# Input_Filter.net
KiCad netlist of a schematic drawn in Altium Designer
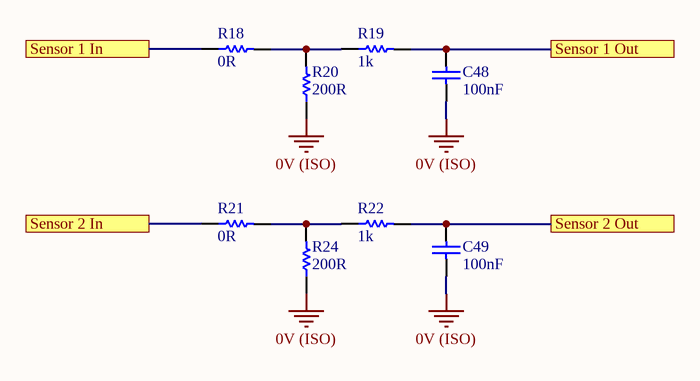
[diagram p0: Input Filter.SchDoc]

(export (version "E")
  (design (tool "Eeschema 10.0.6"))
  (components
    (comp (ref "C48")
      (value "100nF")
      (footprint "0805")
      (fields
        (field (name "PART NUMBER") "GCM21BR71E104KA37L")
        (field (name "TOLERANCE") "10%")
        (field (name "MANUFACTURER") "muRata")
      )
      (libsource (lib "ts_20-standard-library") (part "Capacitor"))
    )
    (comp (ref "C49")
      (value "100nF")
      (footprint "0805")
      (fields
        (field (name "PART NUMBER") "GCM21BR71E104KA37L")
        (field (name "TOLERANCE") "10%")
        (field (name "MANUFACTURER") "muRata")
      )
      (libsource (lib "ts_20-standard-library") (part "Capacitor"))
    )
    (comp (ref "R18")
      (value "0R")
      (footprint "0805")
      (fields
        (field (name "PART NUMBER") "RC0805FR070RL")
        (field (name "MANUFACTURER") "YAGEO")
        (field (name "TOLERANCE") "0.01")
      )
      (libsource (lib "ts_20-standard-library") (part "Resistor"))
    )
    (comp (ref "R19")
      (value "1k")
      (footprint "0805")
      (fields
        (field (name "PART NUMBER") "RC0805FR071KL")
        (field (name "MANUFACTURER") "YAGEO")
        (field (name "TOLERANCE") "0.01")
      )
      (libsource (lib "ts_20-standard-library") (part "Resistor"))
    )
    (comp (ref "R20")
      (value "200R")
      (footprint "0805")
      (fields
        (field (name "PART NUMBER") "RC0805FR07200RL")
        (field (name "MANUFACTURER") "YAGEO")
        (field (name "TOLERANCE") "0.01")
      )
      (libsource (lib "ts_20-standard-library") (part "Resistor"))
    )
    (comp (ref "R21")
      (value "0R")
      (footprint "0805")
      (fields
        (field (name "PART NUMBER") "RC0805FR070RL")
        (field (name "MANUFACTURER") "YAGEO")
        (field (name "TOLERANCE") "0.01")
      )
      (libsource (lib "ts_20-standard-library") (part "Resistor"))
    )
    (comp (ref "R22")
      (value "1k")
      (footprint "0805")
      (fields
        (field (name "PART NUMBER") "RC0805FR071KL")
        (field (name "MANUFACTURER") "YAGEO")
        (field (name "TOLERANCE") "0.01")
      )
      (libsource (lib "ts_20-standard-library") (part "Resistor"))
    )
    (comp (ref "R24")
      (value "200R")
      (footprint "0805")
      (fields
        (field (name "PART NUMBER") "RC0805FR07200RL")
        (field (name "MANUFACTURER") "YAGEO")
        (field (name "TOLERANCE") "0.01")
      )
      (libsource (lib "ts_20-standard-library") (part "Resistor"))
    )
  )
  (nets
    (net (code "1") (name "/Sensor 1 In") (class "Default")
      (node (ref "R18") (pin "1") (pinfunction "1_1") (pintype "passive"))
    )
    (net (code "2") (name "/Sensor 1 Out") (class "Default")
      (node (ref "C48") (pin "2") (pinfunction "2_2") (pintype "passive"))
      (node (ref "R19") (pin "2") (pinfunction "2_2") (pintype "passive"))
    )
    (net (code "3") (name "/Sensor 2 In") (class "Default")
      (node (ref "R21") (pin "1") (pinfunction "1_1") (pintype "passive"))
    )
    (net (code "4") (name "/Sensor 2 Out") (class "Default")
      (node (ref "C49") (pin "2") (pinfunction "2_2") (pintype "passive"))
      (node (ref "R22") (pin "2") (pinfunction "2_2") (pintype "passive"))
    )
    (net (code "5") (name "0V (ISO)") (class "Default")
      (node (ref "C48") (pin "1") (pinfunction "1_1") (pintype "passive"))
      (node (ref "C49") (pin "1") (pinfunction "1_1") (pintype "passive"))
      (node (ref "R20") (pin "1") (pinfunction "1_1") (pintype "passive"))
      (node (ref "R24") (pin "1") (pinfunction "1_1") (pintype "passive"))
    )
    (net (code "6") (name "Net-(R18-Pad2)") (class "Default")
      (node (ref "R18") (pin "2") (pinfunction "2_2") (pintype "passive"))
      (node (ref "R19") (pin "1") (pinfunction "1_1") (pintype "passive"))
      (node (ref "R20") (pin "2") (pinfunction "2_2") (pintype "passive"))
    )
    (net (code "7") (name "Net-(R21-Pad2)") (class "Default")
      (node (ref "R21") (pin "2") (pinfunction "2_2") (pintype "passive"))
      (node (ref "R22") (pin "1") (pinfunction "1_1") (pintype "passive"))
      (node (ref "R24") (pin "2") (pinfunction "2_2") (pintype "passive"))
    )
  )
)
